# BreakawayUSB.net
KiCad netlist of a schematic drawn in Altium Designer
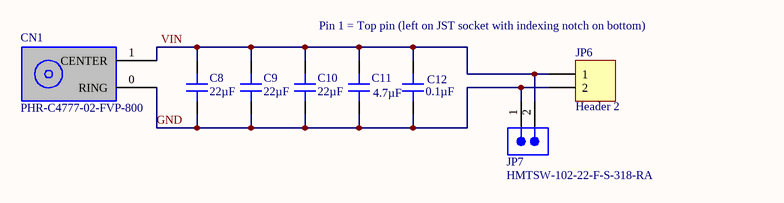
[diagram p0: BreakawayUSB.SchDoc]

(export (version "E")
  (design (tool "Eeschema 10.0.6"))
  (components
    (comp (ref "C8")
      (value "22µF")
      (footprint "CAP 1206_3216 - 1.0MM")
      (description "CAP CER 22UF 10V X5R 1206")
      (fields (field (name "PART NUMBER") "LMK316BJ226MD-T") (field (name "MANUFACTURER") "Taiyo Yuden"))
      (libsource (lib "Celestial Altium Library - altium_library") (part "Capacitor"))
    )
    (comp (ref "C9")
      (value "22µF")
      (footprint "CAP 1206_3216 - 1.0MM")
      (description "CAP CER 22UF 10V X5R 1206")
      (fields (field (name "PART NUMBER") "LMK316BJ226MD-T") (field (name "MANUFACTURER") "Taiyo Yuden"))
      (libsource (lib "Celestial Altium Library - altium_library") (part "Capacitor"))
    )
    (comp (ref "C10")
      (value "22µF")
      (footprint "CAP 1206_3216 - 1.0MM")
      (description "CAP CER 22UF 10V X5R 1206")
      (fields (field (name "PART NUMBER") "LMK316BJ226MD-T") (field (name "MANUFACTURER") "Taiyo Yuden"))
      (libsource (lib "Celestial Altium Library - altium_library") (part "Capacitor"))
    )
    (comp (ref "C11")
      (value "4.7µF")
      (footprint "CAP 1210_3225 - 2.8MM")
      (description "CAP CER 4.7UF 50V X7R 1210")
      (fields (field (name "PART NUMBER") "UMK325B7475KM-T") (field (name "MANUFACTURER") "Taiyo Yuden"))
      (libsource (lib "Celestial Altium Library - altium_library") (part "Capacitor"))
    )
    (comp (ref "C12")
      (value "0.1µF")
      (footprint "CAP 0603_1608")
      (description "CAP CER 0.1UF 50V X7R 0603")
      (fields (field (name "PART NUMBER") "C0603C104K5RAC7411") (field (name "MANUFACTURER") "KEMET"))
      (libsource (lib "Celestial Altium Library - altium_library") (part "Capacitor"))
    )
    (comp (ref "CN1")
      (value "PHR-C4777-02-FVP-800")
      (footprint "PHR-C4777-02-FVP-800")
      (description "Magnetic circular connector")
      (libsource (lib "Voidstar Interconnects") (part "PHR-C4777-02-FVP-800"))
    )
    (comp (ref "JP6")
      (value "Header 2")
      (footprint "HDR1X2")
      (description "Header, 2-Pin")
      (fields (field (name "PUBLISHER") "Altium Limited"))
      (libsource (lib "Miscellaneous Connectors") (part "Header 2"))
    )
    (comp (ref "JP7")
      (value "HMTSW-102-22-F-S-318-RA")
      (footprint "SMTC-HMTSW-102-22-X-S-318-RA")
      (fields (field (name "MANUFACTURER") "Samtec"))
      (libsource (lib "Samtec_2,54_mm_Pitch_Terminal_Strips") (part "HMTSW-102-22-F-S-318-RA"))
    )
  )
  (nets
    (net (code "1") (name "/GND") (class "Default")
      (node (ref "C10") (pin "2") (pinfunction "2_2") (pintype "passive"))
      (node (ref "C11") (pin "1") (pinfunction "1_1") (pintype "passive"))
      (node (ref "C12") (pin "1") (pinfunction "1_1") (pintype "passive"))
      (node (ref "C8") (pin "2") (pinfunction "2_2") (pintype "passive"))
      (node (ref "C9") (pin "2") (pinfunction "2_2") (pintype "passive"))
      (node (ref "CN1") (pin "0") (pinfunction "RING_0") (pintype "passive"))
      (node (ref "JP6") (pin "2") (pinfunction "2_2") (pintype "passive"))
      (node (ref "JP7") (pin "1") (pinfunction "1_1") (pintype "passive"))
    )
    (net (code "2") (name "/VIN") (class "Default")
      (node (ref "C10") (pin "1") (pinfunction "1_1") (pintype "passive"))
      (node (ref "C11") (pin "2") (pinfunction "2_2") (pintype "passive"))
      (node (ref "C12") (pin "2") (pinfunction "2_2") (pintype "passive"))
      (node (ref "C8") (pin "1") (pinfunction "1_1") (pintype "passive"))
      (node (ref "C9") (pin "1") (pinfunction "1_1") (pintype "passive"))
      (node (ref "CN1") (pin "1") (pinfunction "CENTER_1") (pintype "passive"))
      (node (ref "JP6") (pin "1") (pinfunction "1_1") (pintype "passive"))
      (node (ref "JP7") (pin "2") (pinfunction "2_2") (pintype "passive"))
    )
  )
)
